# multisonar.net
KiCad netlist of a schematic drawn in EAGLE
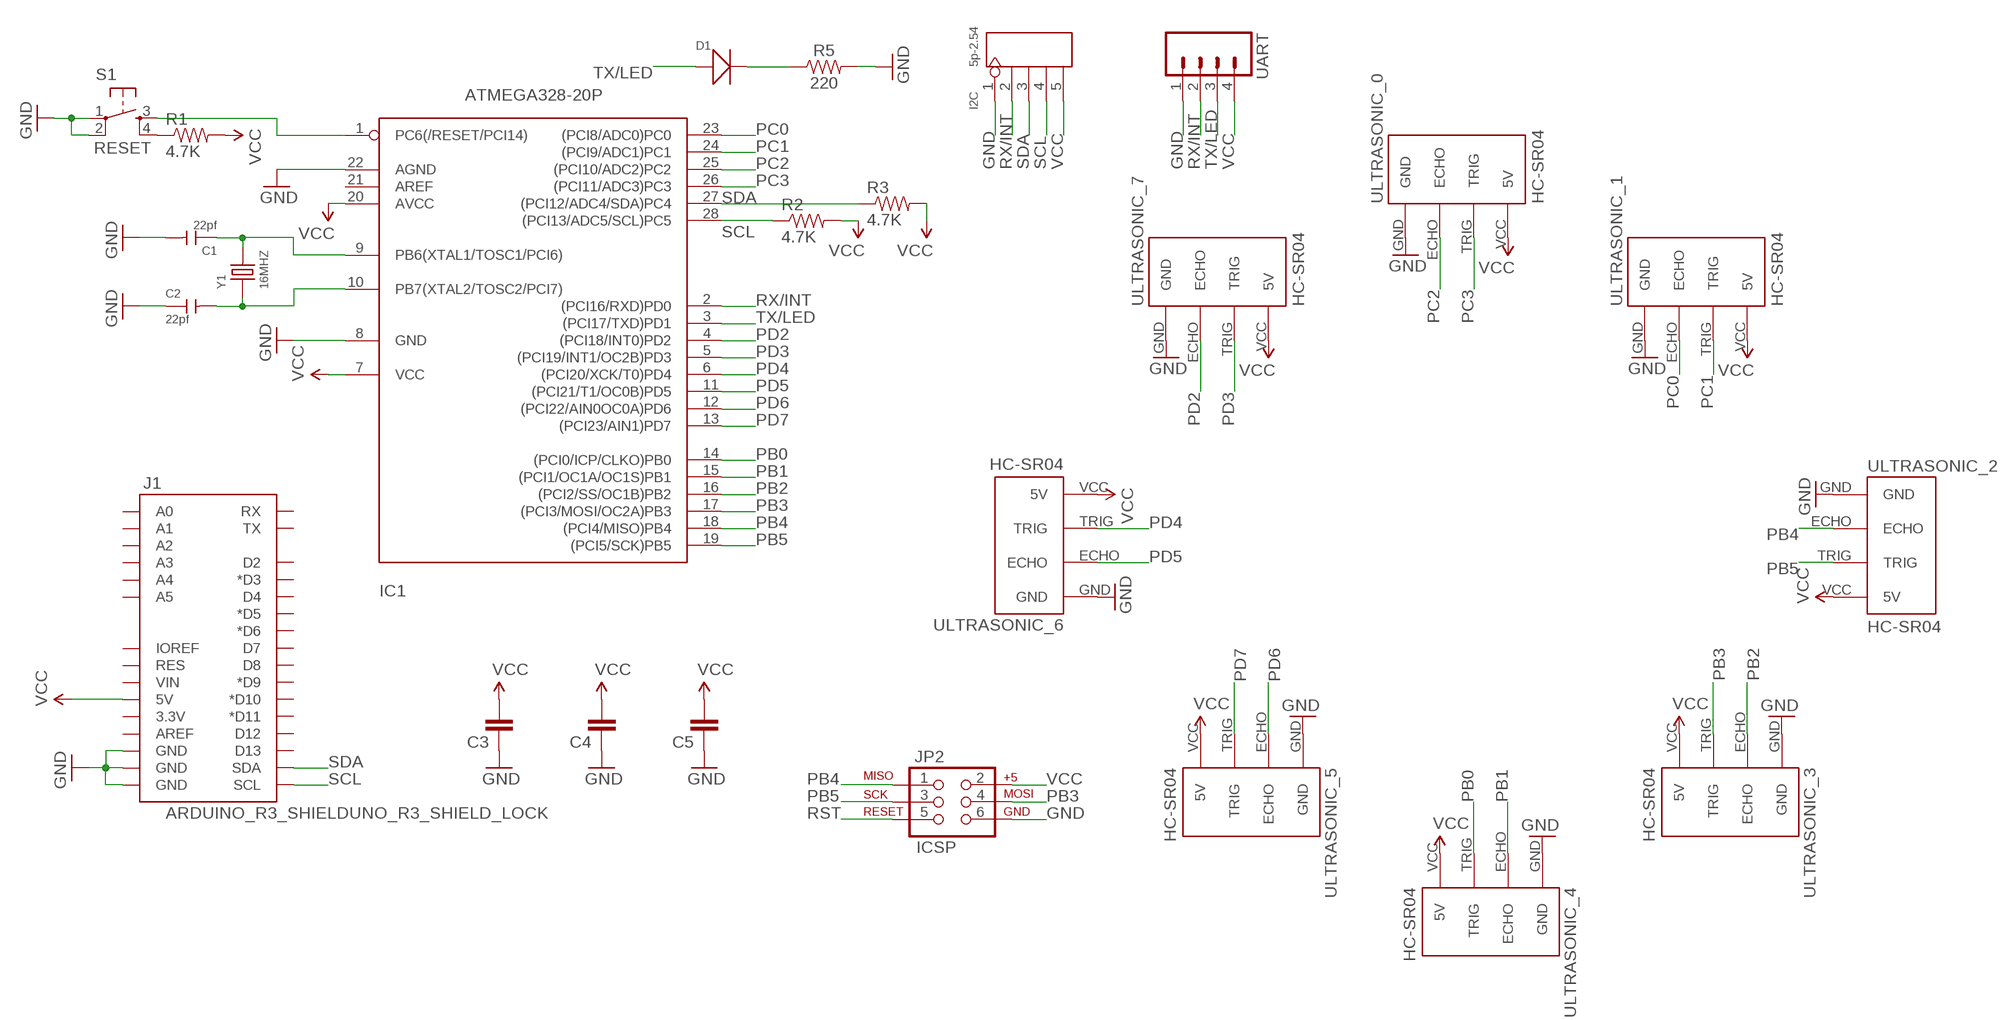
[diagram p0: schematic, sheet 1]

(export (version "E")
  (design (tool "Eeschema 10.0.6"))
  (components
    (comp (ref "C1")
      (value "22pf")
      (footprint "eagle-import:CERAMIC-2.54")
      (fields (field (name "MPN") "CT4-0805CG220J101F3"))
      (libsource (lib "eagle-import") (part "DIP-CERAMIC-22PF-100V-5%-NPO(D5.0MM)"))
    )
    (comp (ref "C2")
      (value "22pf")
      (footprint "eagle-import:CERAMIC-2.54")
      (fields (field (name "MPN") "CT4-0805CG220J101F3"))
      (libsource (lib "eagle-import") (part "DIP-CERAMIC-22PF-100V-5%-NPO(D5.0MM)"))
    )
    (comp (ref "C3")
      (value "0.1UF-50V-20%(PTH)KIT-EZ")
      (footprint "eagle-import:CAP-PTH-SMALL-KIT")
      (libsource (lib "eagle-import") (part "0.1UF-50V-20%(PTH)KIT-EZ"))
    )
    (comp (ref "C4")
      (value "0.1UF-50V-20%(PTH)KIT-EZ")
      (footprint "eagle-import:CAP-PTH-SMALL-KIT")
      (libsource (lib "eagle-import") (part "0.1UF-50V-20%(PTH)KIT-EZ"))
    )
    (comp (ref "C5")
      (value "0.1UF-50V-20%(PTH)KIT-EZ")
      (footprint "eagle-import:CAP-PTH-SMALL-KIT")
      (libsource (lib "eagle-import") (part "0.1UF-50V-20%(PTH)KIT-EZ"))
    )
    (comp (ref "D1")
      (value "DIODE'1206'")
      (footprint "eagle-import:SOD-123")
      (libsource (lib "eagle-import") (part "DIODE'1206'"))
    )
    (comp (ref "I2C")
      (value "5p-2.54")
      (footprint "eagle-import:H5-2.54")
      (fields (field (name "MPN") "F185-1105A0BSYA1"))
      (libsource (lib "eagle-import") (part "DIP-BLACK-FEMALE-HEADER-VERT(5P-2.54)"))
    )
    (comp (ref "IC1")
      (value "ATMEGA328-20P")
      (footprint "eagle-import:DIL28-3")
      (libsource (lib "eagle-import") (part "ATMEGA328P-20"))
    )
    (comp (ref "J1")
      (value "ARDUINO_R3_SHIELDUNO_R3_SHIELD_LOCK")
      (footprint "eagle-import:UNO_R3_SHIELD_LOCK")
      (libsource (lib "eagle-import") (part "ARDUINO_R3_SHIELDUNO_R3_SHIELD_LOCK"))
    )
    (comp (ref "JP2")
      (value "ICSP")
      (footprint "eagle-import:2X3_LOCK")
      (libsource (lib "eagle-import") (part "AVR_SPI_PRG_62X3_LOCK"))
    )
    (comp (ref "R1")
      (value "4.7K")
      (footprint "eagle-import:AXIAL-0.3EZ")
      (libsource (lib "eagle-import") (part "10KOHM-1/4W-1%(PTH)HORIZ-KIT"))
    )
    (comp (ref "R2")
      (value "4.7K")
      (footprint "eagle-import:AXIAL-0.3EZ")
      (libsource (lib "eagle-import") (part "10KOHM-1/4W-1%(PTH)HORIZ-KIT"))
    )
    (comp (ref "R3")
      (value "4.7K")
      (footprint "eagle-import:AXIAL-0.3EZ")
      (libsource (lib "eagle-import") (part "10KOHM-1/4W-1%(PTH)HORIZ-KIT"))
    )
    (comp (ref "R5")
      (value "220")
      (footprint "eagle-import:1206")
      (libsource (lib "eagle-import") (part "RESISTOR1206"))
    )
    (comp (ref "S1")
      (value "RESET")
      (footprint "eagle-import:TAC-SWITCH-PTH")
      (libsource (lib "eagle-import") (part "TACTILE-SWITCH-PTH"))
    )
    (comp (ref "UART")
      (value "M04PTH")
      (footprint "eagle-import:1X04")
      (libsource (lib "eagle-import") (part "M04PTH"))
    )
    (comp (ref "ULTRASONIC_0")
      (value "HC-SR04")
      (footprint "eagle-import:HC-SR04_FOOTPRINT")
      (libsource (lib "eagle-import") (part "HC-SR04"))
    )
    (comp (ref "ULTRASONIC_1")
      (value "HC-SR04")
      (footprint "eagle-import:HC-SR04_FOOTPRINT")
      (libsource (lib "eagle-import") (part "HC-SR04"))
    )
    (comp (ref "ULTRASONIC_2")
      (value "HC-SR04")
      (footprint "eagle-import:HC-SR04_FOOTPRINT")
      (libsource (lib "eagle-import") (part "HC-SR04"))
    )
    (comp (ref "ULTRASONIC_3")
      (value "HC-SR04")
      (footprint "eagle-import:HC-SR04_FOOTPRINT")
      (libsource (lib "eagle-import") (part "HC-SR04"))
    )
    (comp (ref "ULTRASONIC_4")
      (value "HC-SR04")
      (footprint "eagle-import:HC-SR04_FOOTPRINT")
      (libsource (lib "eagle-import") (part "HC-SR04"))
    )
    (comp (ref "ULTRASONIC_5")
      (value "HC-SR04")
      (footprint "eagle-import:HC-SR04_FOOTPRINT")
      (libsource (lib "eagle-import") (part "HC-SR04"))
    )
    (comp (ref "ULTRASONIC_6")
      (value "HC-SR04")
      (footprint "eagle-import:HC-SR04_FOOTPRINT")
      (libsource (lib "eagle-import") (part "HC-SR04"))
    )
    (comp (ref "ULTRASONIC_7")
      (value "HC-SR04")
      (footprint "eagle-import:HC-SR04_FOOTPRINT")
      (libsource (lib "eagle-import") (part "HC-SR04"))
    )
    (comp (ref "Y1")
      (value "16MHZ")
      (footprint "eagle-import:HC49US")
      (fields (field (name "MPN") "HC-49US    16.000MHz"))
      (libsource (lib "eagle-import") (part "DIP-CRYSTAL-16MHZ-18PF-30PPM-40R(HC49US)"))
    )
  )
  (nets
    (net (code "1") (name "/PB0") (class "Default")
      (node (ref "IC1") (pin "14") (pinfunction "(PCI0/ICP/CLKO)PB0_14") (pintype "bidirectional"))
      (node (ref "ULTRASONIC_4") (pin "TRIG") (pinfunction "TRIG_TRIG") (pintype "bidirectional"))
    )
    (net (code "2") (name "/PB1") (class "Default")
      (node (ref "IC1") (pin "15") (pinfunction "(PCI1/OC1A/OC1S)PB1_15") (pintype "bidirectional"))
      (node (ref "ULTRASONIC_4") (pin "ECHO") (pinfunction "ECHO_ECHO") (pintype "bidirectional"))
    )
    (net (code "3") (name "/PB2") (class "Default")
      (node (ref "IC1") (pin "16") (pinfunction "(PCI2/SS/OC1B)PB2_16") (pintype "bidirectional"))
      (node (ref "ULTRASONIC_3") (pin "ECHO") (pinfunction "ECHO_ECHO") (pintype "bidirectional"))
    )
    (net (code "4") (name "/PB3") (class "Default")
      (node (ref "IC1") (pin "17") (pinfunction "(PCI3/MOSI/OC2A)PB3_17") (pintype "bidirectional"))
      (node (ref "JP2") (pin "4") (pinfunction "4_4") (pintype "passive"))
      (node (ref "ULTRASONIC_3") (pin "TRIG") (pinfunction "TRIG_TRIG") (pintype "bidirectional"))
    )
    (net (code "5") (name "/PB4") (class "Default")
      (node (ref "IC1") (pin "18") (pinfunction "(PCI4/MISO)PB4_18") (pintype "bidirectional"))
      (node (ref "JP2") (pin "1") (pinfunction "1_1") (pintype "passive"))
      (node (ref "ULTRASONIC_2") (pin "ECHO") (pinfunction "ECHO_ECHO") (pintype "bidirectional"))
    )
    (net (code "6") (name "/PB5") (class "Default")
      (node (ref "IC1") (pin "19") (pinfunction "(PCI5/SCK)PB5_19") (pintype "bidirectional"))
      (node (ref "JP2") (pin "3") (pinfunction "3_3") (pintype "passive"))
      (node (ref "ULTRASONIC_2") (pin "TRIG") (pinfunction "TRIG_TRIG") (pintype "bidirectional"))
    )
    (net (code "7") (name "/PC0") (class "Default")
      (node (ref "IC1") (pin "23") (pinfunction "(PCI8/ADC0)PC0_23") (pintype "bidirectional"))
      (node (ref "ULTRASONIC_1") (pin "ECHO") (pinfunction "ECHO_ECHO") (pintype "bidirectional"))
    )
    (net (code "8") (name "/PC1") (class "Default")
      (node (ref "IC1") (pin "24") (pinfunction "(PCI9/ADC1)PC1_24") (pintype "bidirectional"))
      (node (ref "ULTRASONIC_1") (pin "TRIG") (pinfunction "TRIG_TRIG") (pintype "bidirectional"))
    )
    (net (code "9") (name "/PC2") (class "Default")
      (node (ref "IC1") (pin "25") (pinfunction "(PCI10/ADC2)PC2_25") (pintype "bidirectional"))
      (node (ref "ULTRASONIC_0") (pin "ECHO") (pinfunction "ECHO_ECHO") (pintype "bidirectional"))
    )
    (net (code "10") (name "/PC3") (class "Default")
      (node (ref "IC1") (pin "26") (pinfunction "(PCI11/ADC3)PC3_26") (pintype "bidirectional"))
      (node (ref "ULTRASONIC_0") (pin "TRIG") (pinfunction "TRIG_TRIG") (pintype "bidirectional"))
    )
    (net (code "11") (name "/PD2") (class "Default")
      (node (ref "IC1") (pin "4") (pinfunction "(PCI18/INT0)PD2_4") (pintype "bidirectional"))
      (node (ref "ULTRASONIC_7") (pin "ECHO") (pinfunction "ECHO_ECHO") (pintype "bidirectional"))
    )
    (net (code "12") (name "/PD3") (class "Default")
      (node (ref "IC1") (pin "5") (pinfunction "(PCI19/INT1/OC2B)PD3_5") (pintype "bidirectional"))
      (node (ref "ULTRASONIC_7") (pin "TRIG") (pinfunction "TRIG_TRIG") (pintype "bidirectional"))
    )
    (net (code "13") (name "/PD4") (class "Default")
      (node (ref "IC1") (pin "6") (pinfunction "(PCI20/XCK/T0)PD4_6") (pintype "bidirectional"))
      (node (ref "ULTRASONIC_6") (pin "TRIG") (pinfunction "TRIG_TRIG") (pintype "bidirectional"))
    )
    (net (code "14") (name "/PD5") (class "Default")
      (node (ref "IC1") (pin "11") (pinfunction "(PCI21/T1/OC0B)PD5_11") (pintype "bidirectional"))
      (node (ref "ULTRASONIC_6") (pin "ECHO") (pinfunction "ECHO_ECHO") (pintype "bidirectional"))
    )
    (net (code "15") (name "/PD6") (class "Default")
      (node (ref "IC1") (pin "12") (pinfunction "(PCI22/AIN0OC0A)PD6_12") (pintype "bidirectional"))
      (node (ref "ULTRASONIC_5") (pin "ECHO") (pinfunction "ECHO_ECHO") (pintype "bidirectional"))
    )
    (net (code "16") (name "/PD7") (class "Default")
      (node (ref "IC1") (pin "13") (pinfunction "(PCI23/AIN1)PD7_13") (pintype "bidirectional"))
      (node (ref "ULTRASONIC_5") (pin "TRIG") (pinfunction "TRIG_TRIG") (pintype "bidirectional"))
    )
    (net (code "17") (name "/RST") (class "Default")
      (node (ref "IC1") (pin "1") (pinfunction "PC6(/RESET/PCI14)_1") (pintype "bidirectional"))
      (node (ref "JP2") (pin "5") (pinfunction "5_5") (pintype "passive"))
      (node (ref "S1") (pin "3") (pinfunction "3_3") (pintype "passive"))
    )
    (net (code "18") (name "/RX{slash}INT") (class "Default")
      (node (ref "I2C") (pin "2") (pinfunction "2_2") (pintype "bidirectional"))
      (node (ref "IC1") (pin "2") (pinfunction "(PCI16/RXD)PD0_2") (pintype "bidirectional"))
      (node (ref "UART") (pin "2") (pinfunction "2_2") (pintype "passive"))
    )
    (net (code "19") (name "/SCL") (class "Default")
      (node (ref "I2C") (pin "4") (pinfunction "4_4") (pintype "bidirectional"))
      (node (ref "IC1") (pin "28") (pinfunction "(PCI13/ADC5/SCL)PC5_28") (pintype "bidirectional"))
      (node (ref "J1") (pin "SCL") (pinfunction "SCL_SCL") (pintype "bidirectional"))
      (node (ref "R2") (pin "P$1") (pinfunction "1_P$1") (pintype "passive"))
    )
    (net (code "20") (name "/SDA") (class "Default")
      (node (ref "I2C") (pin "3") (pinfunction "3_3") (pintype "bidirectional"))
      (node (ref "IC1") (pin "27") (pinfunction "(PCI12/ADC4/SDA)PC4_27") (pintype "bidirectional"))
      (node (ref "J1") (pin "SDA") (pinfunction "SDA_SDA") (pintype "bidirectional"))
      (node (ref "R3") (pin "P$1") (pinfunction "1_P$1") (pintype "passive"))
    )
    (net (code "21") (name "/TX{slash}LED") (class "Default")
      (node (ref "D1") (pin "+") (pinfunction "+_+") (pintype "passive"))
      (node (ref "IC1") (pin "3") (pinfunction "(PCI17/TXD)PD1_3") (pintype "bidirectional"))
      (node (ref "UART") (pin "3") (pinfunction "3_3") (pintype "passive"))
    )
    (net (code "22") (name "GND") (class "Default")
      (node (ref "C1") (pin "2") (pinfunction "2_2") (pintype "passive"))
      (node (ref "C2") (pin "1") (pinfunction "1_1") (pintype "passive"))
      (node (ref "C3") (pin "1") (pinfunction "1_1") (pintype "passive"))
      (node (ref "C4") (pin "1") (pinfunction "1_1") (pintype "passive"))
      (node (ref "C5") (pin "1") (pinfunction "1_1") (pintype "passive"))
      (node (ref "I2C") (pin "1") (pinfunction "1_1") (pintype "bidirectional"))
      (node (ref "IC1") (pin "22") (pinfunction "AGND_22") (pintype "bidirectional"))
      (node (ref "IC1") (pin "8") (pinfunction "GND_8") (pintype "bidirectional"))
      (node (ref "J1") (pin "GND@0") (pinfunction "GND_GND@0") (pintype "bidirectional"))
      (node (ref "J1") (pin "GND@1") (pinfunction "GND_GND@1") (pintype "bidirectional"))
      (node (ref "J1") (pin "GND@2") (pinfunction "GND_GND@2") (pintype "bidirectional"))
      (node (ref "JP2") (pin "6") (pinfunction "6_6") (pintype "passive"))
      (node (ref "R5") (pin "2") (pinfunction "2_2") (pintype "passive"))
      (node (ref "S1") (pin "1") (pinfunction "1_1") (pintype "passive"))
      (node (ref "S1") (pin "2") (pinfunction "2_2") (pintype "passive"))
      (node (ref "UART") (pin "1") (pinfunction "1_1") (pintype "passive"))
      (node (ref "ULTRASONIC_0") (pin "GND") (pinfunction "GND_GND") (pintype "bidirectional"))
      (node (ref "ULTRASONIC_1") (pin "GND") (pinfunction "GND_GND") (pintype "bidirectional"))
      (node (ref "ULTRASONIC_2") (pin "GND") (pinfunction "GND_GND") (pintype "bidirectional"))
      (node (ref "ULTRASONIC_3") (pin "GND") (pinfunction "GND_GND") (pintype "bidirectional"))
      (node (ref "ULTRASONIC_4") (pin "GND") (pinfunction "GND_GND") (pintype "bidirectional"))
      (node (ref "ULTRASONIC_5") (pin "GND") (pinfunction "GND_GND") (pintype "bidirectional"))
      (node (ref "ULTRASONIC_6") (pin "GND") (pinfunction "GND_GND") (pintype "bidirectional"))
      (node (ref "ULTRASONIC_7") (pin "GND") (pinfunction "GND_GND") (pintype "bidirectional"))
    )
    (net (code "23") (name "Net-(D1-Pad-)") (class "Default")
      (node (ref "D1") (pin "-") (pinfunction "-_-") (pintype "passive"))
      (node (ref "R5") (pin "1") (pinfunction "1_1") (pintype "passive"))
    )
    (net (code "24") (name "Net-(IC1-PB6(XTAL1{slash}TOSC1{slash}PCI6))") (class "Default")
      (node (ref "C1") (pin "1") (pinfunction "1_1") (pintype "passive"))
      (node (ref "IC1") (pin "9") (pinfunction "PB6(XTAL1/TOSC1/PCI6)_9") (pintype "bidirectional"))
      (node (ref "Y1") (pin "2") (pinfunction "2_2") (pintype "passive"))
    )
    (net (code "25") (name "Net-(IC1-PB7(XTAL2{slash}TOSC2{slash}PCI7))") (class "Default")
      (node (ref "C2") (pin "2") (pinfunction "2_2") (pintype "passive"))
      (node (ref "IC1") (pin "10") (pinfunction "PB7(XTAL2/TOSC2/PCI7)_10") (pintype "bidirectional"))
      (node (ref "Y1") (pin "1") (pinfunction "1_1") (pintype "passive"))
    )
    (net (code "26") (name "Net-(R1-1)") (class "Default")
      (node (ref "R1") (pin "P$1") (pinfunction "1_P$1") (pintype "passive"))
      (node (ref "S1") (pin "4") (pinfunction "4_4") (pintype "passive"))
    )
    (net (code "27") (name "VCC") (class "Default")
      (node (ref "C3") (pin "2") (pinfunction "2_2") (pintype "passive"))
      (node (ref "C4") (pin "2") (pinfunction "2_2") (pintype "passive"))
      (node (ref "C5") (pin "2") (pinfunction "2_2") (pintype "passive"))
      (node (ref "I2C") (pin "5") (pinfunction "5_5") (pintype "bidirectional"))
      (node (ref "IC1") (pin "20") (pinfunction "AVCC_20") (pintype "bidirectional"))
      (node (ref "IC1") (pin "7") (pinfunction "VCC_7") (pintype "bidirectional"))
      (node (ref "J1") (pin "5V") (pinfunction "5V_5V") (pintype "bidirectional"))
      (node (ref "JP2") (pin "2") (pinfunction "2_2") (pintype "passive"))
      (node (ref "R1") (pin "P$2") (pinfunction "2_P$2") (pintype "passive"))
      (node (ref "R2") (pin "P$2") (pinfunction "2_P$2") (pintype "passive"))
      (node (ref "R3") (pin "P$2") (pinfunction "2_P$2") (pintype "passive"))
      (node (ref "UART") (pin "4") (pinfunction "4_4") (pintype "passive"))
      (node (ref "ULTRASONIC_0") (pin "VCC") (pinfunction "5V_VCC") (pintype "bidirectional"))
      (node (ref "ULTRASONIC_1") (pin "VCC") (pinfunction "5V_VCC") (pintype "bidirectional"))
      (node (ref "ULTRASONIC_2") (pin "VCC") (pinfunction "5V_VCC") (pintype "bidirectional"))
      (node (ref "ULTRASONIC_3") (pin "VCC") (pinfunction "5V_VCC") (pintype "bidirectional"))
      (node (ref "ULTRASONIC_4") (pin "VCC") (pinfunction "5V_VCC") (pintype "bidirectional"))
      (node (ref "ULTRASONIC_5") (pin "VCC") (pinfunction "5V_VCC") (pintype "bidirectional"))
      (node (ref "ULTRASONIC_6") (pin "VCC") (pinfunction "5V_VCC") (pintype "bidirectional"))
      (node (ref "ULTRASONIC_7") (pin "VCC") (pinfunction "5V_VCC") (pintype "bidirectional"))
    )
    (net (code "28") (name "unconnected-(IC1-AREF-Pad21)") (class "Default")
      (node (ref "IC1") (pin "21") (pinfunction "AREF_21") (pintype "bidirectional"))
    )
    (net (code "29") (name "unconnected-(J1-*D3-PadD3)") (class "Default")
      (node (ref "J1") (pin "D3") (pinfunction "*D3_D3") (pintype "bidirectional"))
    )
    (net (code "30") (name "unconnected-(J1-*D5-PadD5)") (class "Default")
      (node (ref "J1") (pin "D5") (pinfunction "*D5_D5") (pintype "bidirectional"))
    )
    (net (code "31") (name "unconnected-(J1-*D6-PadD6)") (class "Default")
      (node (ref "J1") (pin "D6") (pinfunction "*D6_D6") (pintype "bidirectional"))
    )
    (net (code "32") (name "unconnected-(J1-*D9-PadD9)") (class "Default")
      (node (ref "J1") (pin "D9") (pinfunction "*D9_D9") (pintype "bidirectional"))
    )
    (net (code "33") (name "unconnected-(J1-*D10-PadD10)") (class "Default")
      (node (ref "J1") (pin "D10") (pinfunction "*D10_D10") (pintype "bidirectional"))
    )
    (net (code "34") (name "unconnected-(J1-*D11-PadD11)") (class "Default")
      (node (ref "J1") (pin "D11") (pinfunction "*D11_D11") (pintype "bidirectional"))
    )
    (net (code "35") (name "unconnected-(J1-Pad3.3V)") (class "Default")
      (node (ref "J1") (pin "3.3V") (pinfunction "3.3V_3.3V") (pintype "bidirectional"))
    )
    (net (code "36") (name "unconnected-(J1-PadA0)") (class "Default")
      (node (ref "J1") (pin "A0") (pinfunction "A0_A0") (pintype "bidirectional"))
    )
    (net (code "37") (name "unconnected-(J1-PadA1)") (class "Default")
      (node (ref "J1") (pin "A1") (pinfunction "A1_A1") (pintype "bidirectional"))
    )
    (net (code "38") (name "unconnected-(J1-PadA2)") (class "Default")
      (node (ref "J1") (pin "A2") (pinfunction "A2_A2") (pintype "bidirectional"))
    )
    (net (code "39") (name "unconnected-(J1-PadA3)") (class "Default")
      (node (ref "J1") (pin "A3") (pinfunction "A3_A3") (pintype "bidirectional"))
    )
    (net (code "40") (name "unconnected-(J1-PadA4)") (class "Default")
      (node (ref "J1") (pin "A4") (pinfunction "A4_A4") (pintype "bidirectional"))
    )
    (net (code "41") (name "unconnected-(J1-PadA5)") (class "Default")
      (node (ref "J1") (pin "A5") (pinfunction "A5_A5") (pintype "bidirectional"))
    )
    (net (code "42") (name "unconnected-(J1-PadAREF)") (class "Default")
      (node (ref "J1") (pin "AREF") (pinfunction "AREF_AREF") (pintype "bidirectional"))
    )
    (net (code "43") (name "unconnected-(J1-PadD2)") (class "Default")
      (node (ref "J1") (pin "D2") (pinfunction "D2_D2") (pintype "bidirectional"))
    )
    (net (code "44") (name "unconnected-(J1-PadD4)") (class "Default")
      (node (ref "J1") (pin "D4") (pinfunction "D4_D4") (pintype "bidirectional"))
    )
    (net (code "45") (name "unconnected-(J1-PadD7)") (class "Default")
      (node (ref "J1") (pin "D7") (pinfunction "D7_D7") (pintype "bidirectional"))
    )
    (net (code "46") (name "unconnected-(J1-PadD8)") (class "Default")
      (node (ref "J1") (pin "D8") (pinfunction "D8_D8") (pintype "bidirectional"))
    )
    (net (code "47") (name "unconnected-(J1-PadD12)") (class "Default")
      (node (ref "J1") (pin "D12") (pinfunction "D12_D12") (pintype "bidirectional"))
    )
    (net (code "48") (name "unconnected-(J1-PadD13)") (class "Default")
      (node (ref "J1") (pin "D13") (pinfunction "D13_D13") (pintype "bidirectional"))
    )
    (net (code "49") (name "unconnected-(J1-PadIOREF)") (class "Default")
      (node (ref "J1") (pin "IOREF") (pinfunction "IOREF_IOREF") (pintype "bidirectional"))
    )
    (net (code "50") (name "unconnected-(J1-PadRES)") (class "Default")
      (node (ref "J1") (pin "RES") (pinfunction "RES_RES") (pintype "bidirectional"))
    )
    (net (code "51") (name "unconnected-(J1-PadRX)") (class "Default")
      (node (ref "J1") (pin "RX") (pinfunction "RX_RX") (pintype "bidirectional"))
    )
    (net (code "52") (name "unconnected-(J1-PadTX)") (class "Default")
      (node (ref "J1") (pin "TX") (pinfunction "TX_TX") (pintype "bidirectional"))
    )
    (net (code "53") (name "unconnected-(J1-PadVIN)") (class "Default")
      (node (ref "J1") (pin "VIN") (pinfunction "VIN_VIN") (pintype "bidirectional"))
    )
  )
)
